# RFM95W.net
KiCad netlist of a schematic drawn in Altium Designer
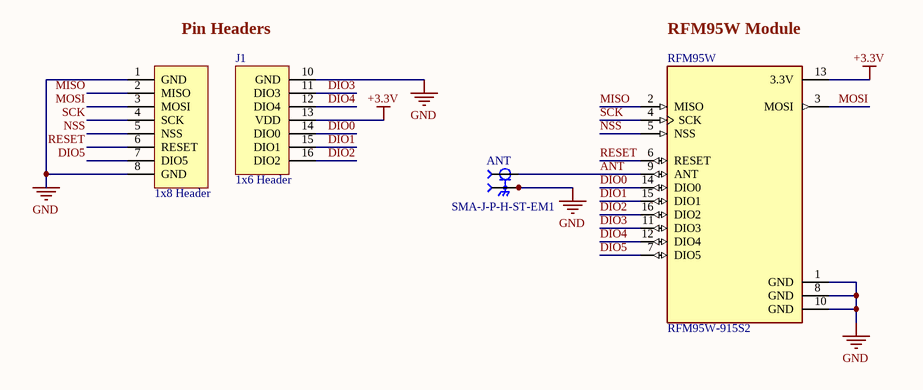
[diagram p0: RFM95W.SchDoc]

(export (version "E")
  (design (tool "Eeschema 10.0.6"))
  (components
    (comp (ref "ANT")
      (value "SMA-J-P-H-ST-EM1")
      (footprint "SAMTEC_SMA-J-P-H-ST-EM1")
      (description "SMA Connector Jack, Female Socket 50Ohm Board Edge, End Launch Solder")
      (fields (field (name "MF") "Samtec") (field (name "DIGI-KEY_PART_NUMBER") "SAM8857-ND"))
      (libsource (lib "SnapEDAsch") (part "SMA-J-P-H-ST-EM1"))
    )
    (comp (ref "J1")
      (value "1x6 Header")
      (footprint "HDR1X7")
      (description "CONN HEADER VERT 7POS 2.54MM")
      (fields (field (name "MANUFACTURER") "Molex") (field (name "MANUFACTURER PART NUMBER") "22-10-2061"))
      (libsource (lib "RFM95W_Schlib") (part "22-10-2061_1"))
    )
    (comp (ref "J2")
      (value "1x8 Header")
      (footprint "HDR1X8")
      (description "CONN HEADER VERT 8POS 2.54MM")
      (fields (field (name "MANUFACTURER") "Molex") (field (name "MANUFACTURER PART NUMBER") "22-10-2061"))
      (libsource (lib "RFM95W_Schlib") (part "22-10-2061"))
    )
    (comp (ref "RFM95W")
      (value "RFM95W-915S2")
      (footprint "XCVR_RFM95W-915S2")
      (description "RFM95(W) - Low Power Long Range Transceiver Module V1.0")
      (fields (field (name "MF") "{'manufacturer': u'RF Solutions'}"))
      (libsource (lib "SnapEDA_Library") (part "RFM95W-915S2"))
    )
  )
  (nets
    (net (code "1") (name "+3.3V") (class "Default")
      (node (ref "J1") (pin "13") (pinfunction "VDD_13") (pintype "passive"))
      (node (ref "RFM95W") (pin "13") (pinfunction "3.3V_13") (pintype "power_in"))
    )
    (net (code "2") (name "/ANT") (class "Default")
      (node (ref "ANT") (pin "1") (pinfunction "1_1") (pintype "passive"))
      (node (ref "RFM95W") (pin "9") (pinfunction "ANT_9") (pintype "bidirectional"))
    )
    (net (code "3") (name "/DIO0") (class "Default")
      (node (ref "J1") (pin "14") (pinfunction "DIO0_14") (pintype "passive"))
      (node (ref "RFM95W") (pin "14") (pinfunction "DIO0_14") (pintype "bidirectional"))
    )
    (net (code "4") (name "/DIO1") (class "Default")
      (node (ref "J1") (pin "15") (pinfunction "DIO1_15") (pintype "passive"))
      (node (ref "RFM95W") (pin "15") (pinfunction "DIO1_15") (pintype "bidirectional"))
    )
    (net (code "5") (name "/DIO2") (class "Default")
      (node (ref "J1") (pin "16") (pinfunction "DIO2_16") (pintype "passive"))
      (node (ref "RFM95W") (pin "16") (pinfunction "DIO2_16") (pintype "bidirectional"))
    )
    (net (code "6") (name "/DIO3") (class "Default")
      (node (ref "J1") (pin "11") (pinfunction "DIO3_11") (pintype "passive"))
      (node (ref "RFM95W") (pin "11") (pinfunction "DIO3_11") (pintype "bidirectional"))
    )
    (net (code "7") (name "/DIO4") (class "Default")
      (node (ref "J1") (pin "12") (pinfunction "DIO4_12") (pintype "passive"))
      (node (ref "RFM95W") (pin "12") (pinfunction "DIO4_12") (pintype "bidirectional"))
    )
    (net (code "8") (name "/DIO5") (class "Default")
      (node (ref "J2") (pin "7") (pinfunction "DIO5_7") (pintype "passive"))
      (node (ref "RFM95W") (pin "7") (pinfunction "DIO5_7") (pintype "bidirectional"))
    )
    (net (code "9") (name "/MISO") (class "Default")
      (node (ref "J2") (pin "2") (pinfunction "MISO_2") (pintype "passive"))
      (node (ref "RFM95W") (pin "2") (pinfunction "MISO_2") (pintype "input"))
    )
    (net (code "10") (name "/MOSI") (class "Default")
      (node (ref "J2") (pin "3") (pinfunction "MOSI_3") (pintype "passive"))
      (node (ref "RFM95W") (pin "3") (pinfunction "MOSI_3") (pintype "output"))
    )
    (net (code "11") (name "/NSS") (class "Default")
      (node (ref "J2") (pin "5") (pinfunction "NSS_5") (pintype "passive"))
      (node (ref "RFM95W") (pin "5") (pinfunction "NSS_5") (pintype "input"))
    )
    (net (code "12") (name "/RESET") (class "Default")
      (node (ref "J2") (pin "6") (pinfunction "RESET_6") (pintype "passive"))
      (node (ref "RFM95W") (pin "6") (pinfunction "RESET_6") (pintype "bidirectional"))
    )
    (net (code "13") (name "/SCK") (class "Default")
      (node (ref "J2") (pin "4") (pinfunction "SCK_4") (pintype "passive"))
      (node (ref "RFM95W") (pin "4") (pinfunction "SCK_4") (pintype "input"))
    )
    (net (code "14") (name "GND") (class "Default")
      (node (ref "ANT") (pin "2_1") (pinfunction "2_2_1") (pintype "passive"))
      (node (ref "ANT") (pin "2_2") (pinfunction "2_2_2") (pintype "passive"))
      (node (ref "ANT") (pin "3_1") (pinfunction "2_3_1") (pintype "passive"))
      (node (ref "ANT") (pin "3_2") (pinfunction "2_3_2") (pintype "passive"))
      (node (ref "J1") (pin "10") (pinfunction "GND_10") (pintype "passive"))
      (node (ref "J2") (pin "1") (pinfunction "GND_1") (pintype "passive"))
      (node (ref "J2") (pin "8") (pinfunction "GND_8") (pintype "passive"))
      (node (ref "RFM95W") (pin "1") (pinfunction "GND_1") (pintype "power_in"))
      (node (ref "RFM95W") (pin "10") (pinfunction "GND_10") (pintype "power_in"))
      (node (ref "RFM95W") (pin "8") (pinfunction "GND_8") (pintype "power_in"))
    )
  )
)
